# microphone.net
KiCad netlist of a schematic drawn in EAGLE
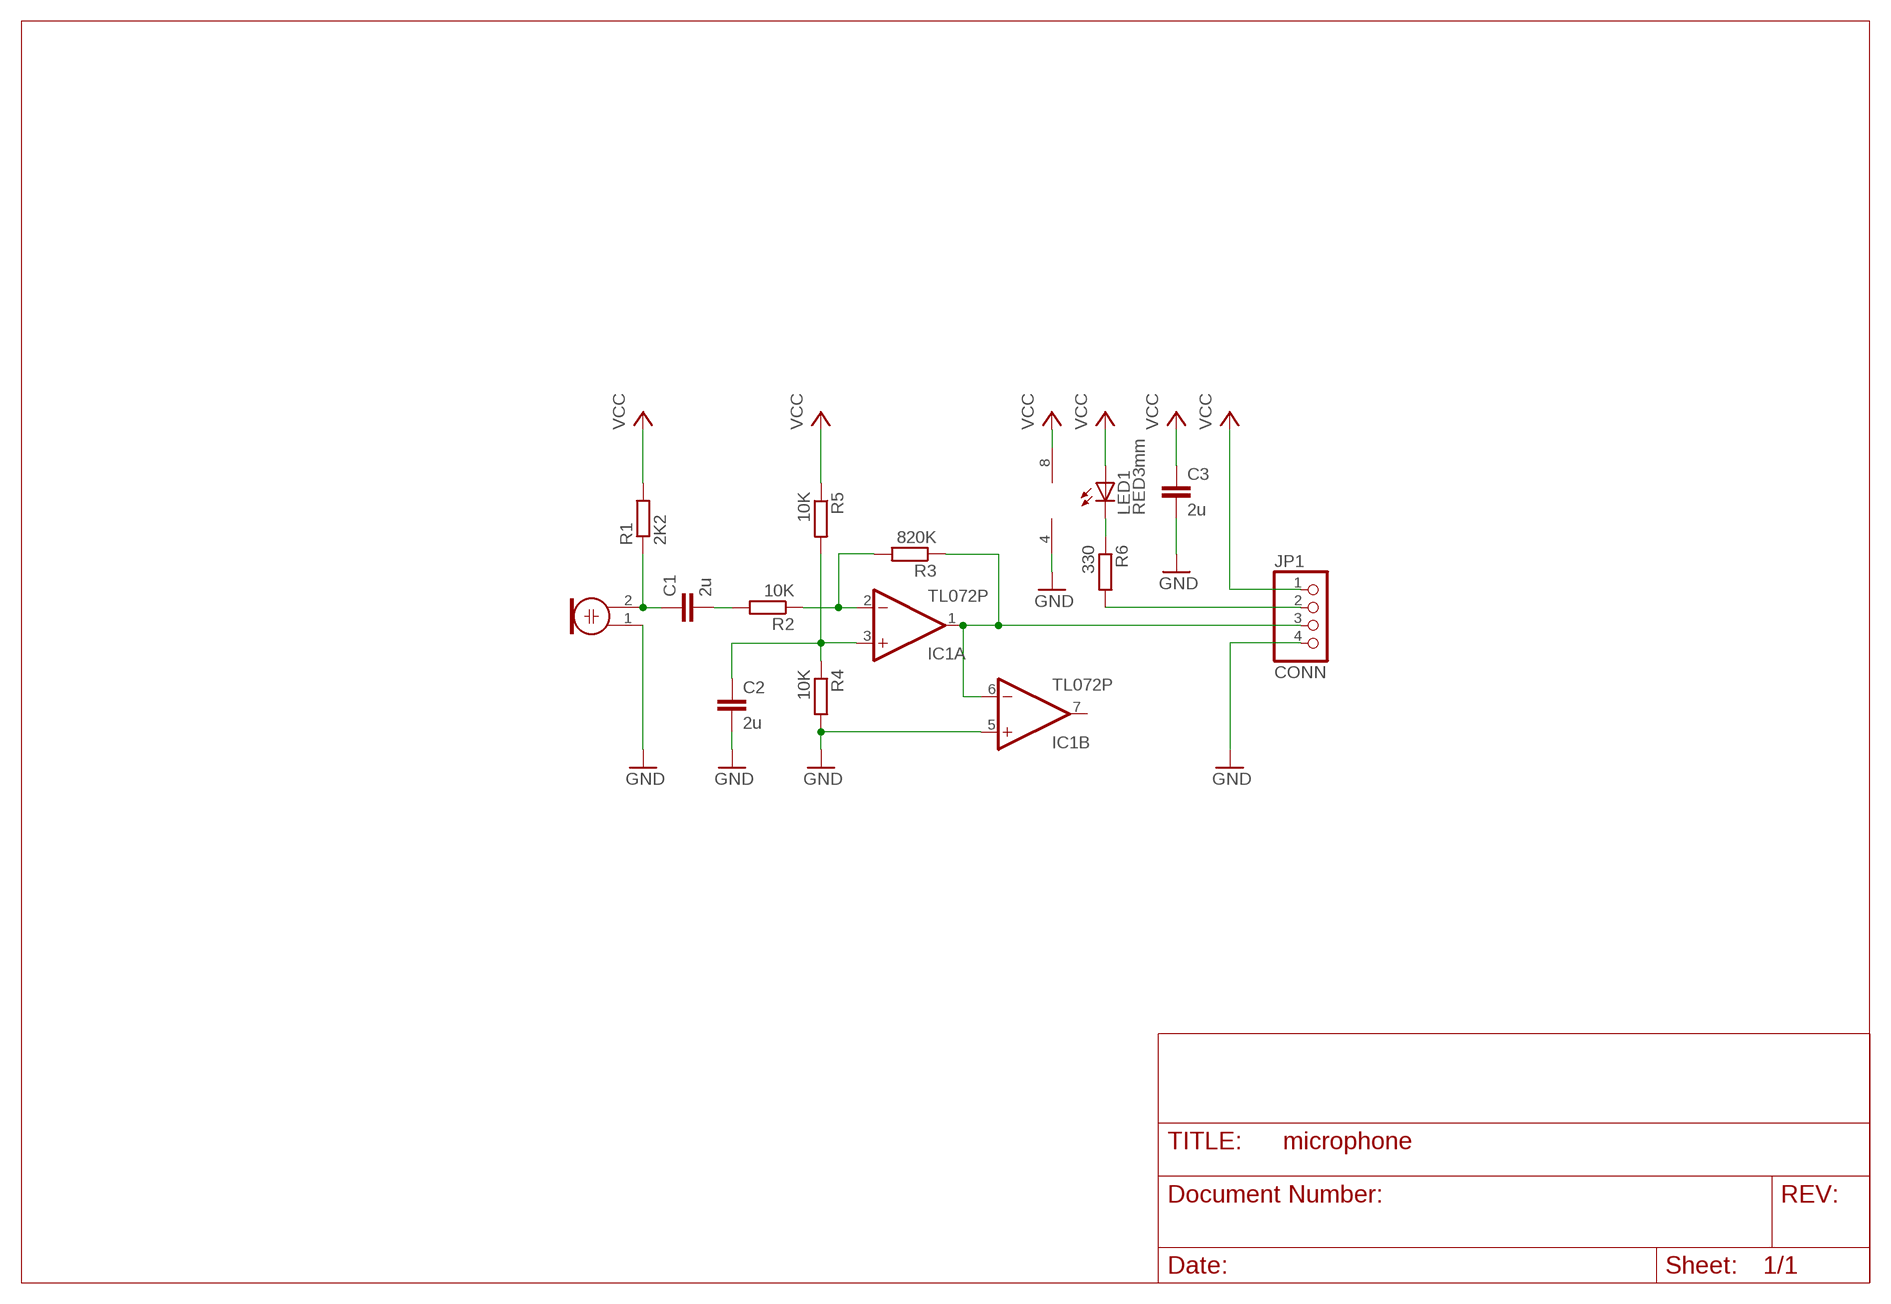
[diagram p0: schematic, sheet 1]

(export (version "E")
  (design (tool "Eeschema 10.0.6"))
  (components
    (comp (ref "C1")
      (value "2u")
      (footprint "eagle-import:C050-025X075")
      (libsource (lib "eagle-import") (part "C-EU050-025X075"))
    )
    (comp (ref "C2")
      (value "2u")
      (footprint "eagle-import:C025-025X050")
      (libsource (lib "eagle-import") (part "C-EU025-025X050"))
    )
    (comp (ref "C3")
      (value "2u")
      (footprint "eagle-import:C075-032X103")
      (libsource (lib "eagle-import") (part "C-EU075-032X103"))
    )
    (comp (ref "IC1")
      (value "TL072P")
      (footprint "eagle-import:DIL08")
      (libsource (lib "eagle-import") (part "TL072P"))
    )
    (comp (ref "JP1")
      (value "CONN")
      (footprint "eagle-import:1X04")
      (libsource (lib "eagle-import") (part "PINHD-1X4"))
    )
    (comp (ref "LED1")
      (value "RED3mm")
      (footprint "eagle-import:LED5MM")
      (libsource (lib "eagle-import") (part "LED5MM"))
    )
    (comp (ref "M1")
      (value "ELECTRET_MICROPHON-F6035AP")
      (footprint "eagle-import:F6035AP")
      (libsource (lib "eagle-import") (part "ELECTRET_MICROPHON-F6035AP"))
    )
    (comp (ref "R1")
      (value "2K2")
      (footprint "eagle-import:0204_7")
      (libsource (lib "eagle-import") (part "R-EU_0204/7"))
    )
    (comp (ref "R2")
      (value "10K")
      (footprint "eagle-import:0204V")
      (libsource (lib "eagle-import") (part "R-EU_0204/2V"))
    )
    (comp (ref "R3")
      (value "820K")
      (footprint "eagle-import:0204V")
      (libsource (lib "eagle-import") (part "R-EU_0204/2V"))
    )
    (comp (ref "R4")
      (value "10K")
      (footprint "eagle-import:0204V")
      (libsource (lib "eagle-import") (part "R-EU_0204/2V"))
    )
    (comp (ref "R5")
      (value "10K")
      (footprint "eagle-import:0204_7")
      (libsource (lib "eagle-import") (part "R-EU_0204/7"))
    )
    (comp (ref "R6")
      (value "330")
      (footprint "eagle-import:0204_7")
      (libsource (lib "eagle-import") (part "R-EU_0204/7"))
    )
  )
  (nets
    (net (code "1") (name "GND") (class "Default")
      (node (ref "C2") (pin "2") (pinfunction "2_2") (pintype "passive"))
      (node (ref "C3") (pin "2") (pinfunction "2_2") (pintype "passive"))
      (node (ref "IC1") (pin "4") (pinfunction "V-_4") (pintype "power_in"))
      (node (ref "IC1") (pin "5") (pinfunction "+IN_5") (pintype "input"))
      (node (ref "JP1") (pin "4") (pinfunction "4_4") (pintype "passive"))
      (node (ref "M1") (pin "1") (pinfunction "1_1") (pintype "passive"))
      (node (ref "R4") (pin "2") (pinfunction "2_2") (pintype "passive"))
    )
    (net (code "2") (name "Net-(C1-Pad1)") (class "Default")
      (node (ref "C1") (pin "1") (pinfunction "1_1") (pintype "passive"))
      (node (ref "M1") (pin "2") (pinfunction "2_2") (pintype "passive"))
      (node (ref "R1") (pin "1") (pinfunction "1_1") (pintype "passive"))
    )
    (net (code "3") (name "Net-(C1-Pad2)") (class "Default")
      (node (ref "C1") (pin "2") (pinfunction "2_2") (pintype "passive"))
      (node (ref "R2") (pin "2") (pinfunction "2_2") (pintype "passive"))
    )
    (net (code "4") (name "Net-(IC1A-+IN)") (class "Default")
      (node (ref "C2") (pin "1") (pinfunction "1_1") (pintype "passive"))
      (node (ref "IC1") (pin "3") (pinfunction "+IN_3") (pintype "input"))
      (node (ref "R4") (pin "1") (pinfunction "1_1") (pintype "passive"))
      (node (ref "R5") (pin "2") (pinfunction "2_2") (pintype "passive"))
    )
    (net (code "5") (name "Net-(IC1A--IN)") (class "Default")
      (node (ref "IC1") (pin "2") (pinfunction "-IN_2") (pintype "input"))
      (node (ref "R2") (pin "1") (pinfunction "1_1") (pintype "passive"))
      (node (ref "R3") (pin "2") (pinfunction "2_2") (pintype "passive"))
    )
    (net (code "6") (name "Net-(IC1A-OUT)") (class "Default")
      (node (ref "IC1") (pin "1") (pinfunction "OUT_1") (pintype "output"))
      (node (ref "IC1") (pin "6") (pinfunction "-IN_6") (pintype "input"))
      (node (ref "JP1") (pin "3") (pinfunction "3_3") (pintype "passive"))
      (node (ref "R3") (pin "1") (pinfunction "1_1") (pintype "passive"))
    )
    (net (code "7") (name "Net-(JP1-Pad2)") (class "Default")
      (node (ref "JP1") (pin "2") (pinfunction "2_2") (pintype "passive"))
      (node (ref "R6") (pin "2") (pinfunction "2_2") (pintype "passive"))
    )
    (net (code "8") (name "Net-(LED1-C)") (class "Default")
      (node (ref "LED1") (pin "K") (pinfunction "C_K") (pintype "passive"))
      (node (ref "R6") (pin "1") (pinfunction "1_1") (pintype "passive"))
    )
    (net (code "9") (name "VCC") (class "Default")
      (node (ref "C3") (pin "1") (pinfunction "1_1") (pintype "passive"))
      (node (ref "IC1") (pin "8") (pinfunction "V+_8") (pintype "power_in"))
      (node (ref "JP1") (pin "1") (pinfunction "1_1") (pintype "passive"))
      (node (ref "LED1") (pin "A") (pinfunction "A_A") (pintype "passive"))
      (node (ref "R1") (pin "2") (pinfunction "2_2") (pintype "passive"))
      (node (ref "R5") (pin "1") (pinfunction "1_1") (pintype "passive"))
    )
    (net (code "10") (name "unconnected-(IC1B-OUT-Pad7)") (class "Default")
      (node (ref "IC1") (pin "7") (pinfunction "OUT_7") (pintype "output"))
    )
  )
)
